# Routerv1_1.net
KiCad netlist of a schematic drawn in EAGLE
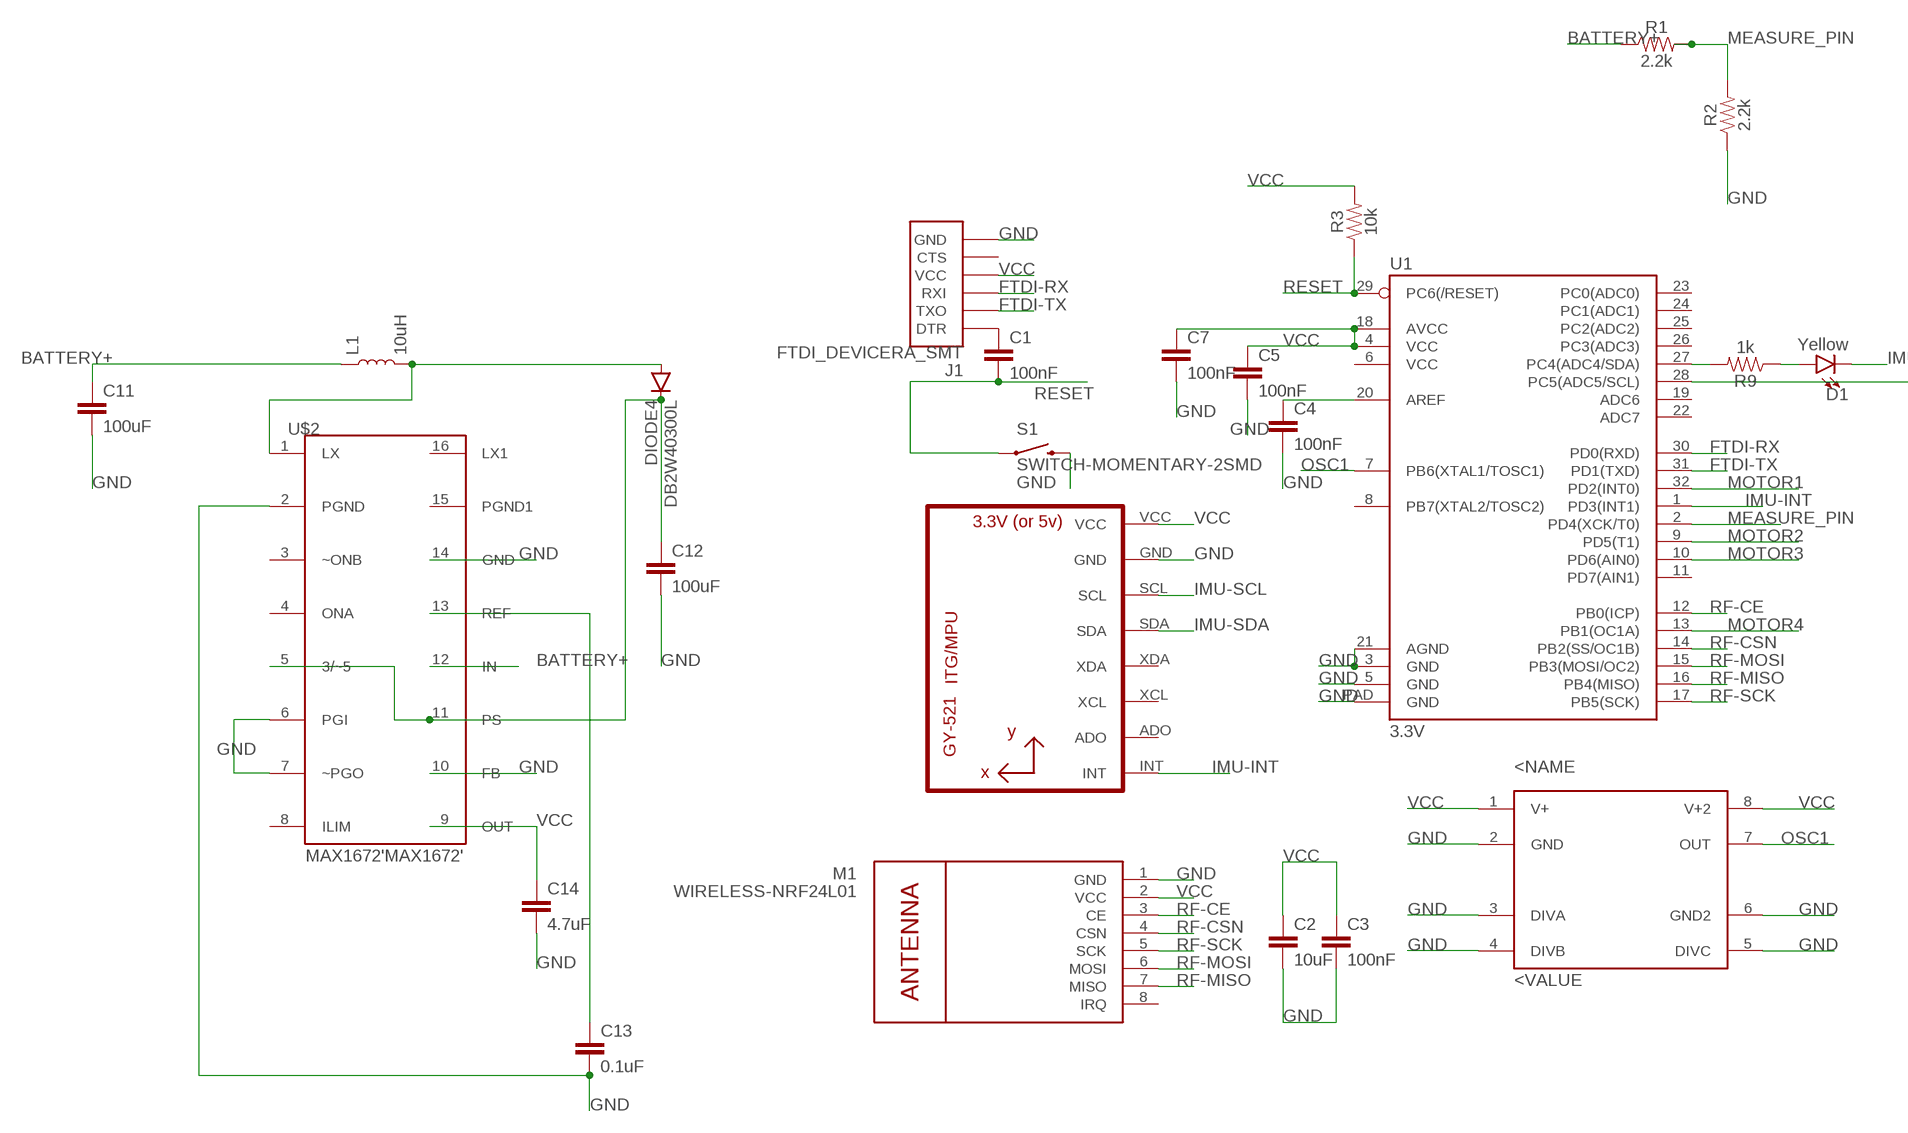
[diagram p0: schematic, sheet 1, part 1 of 2]
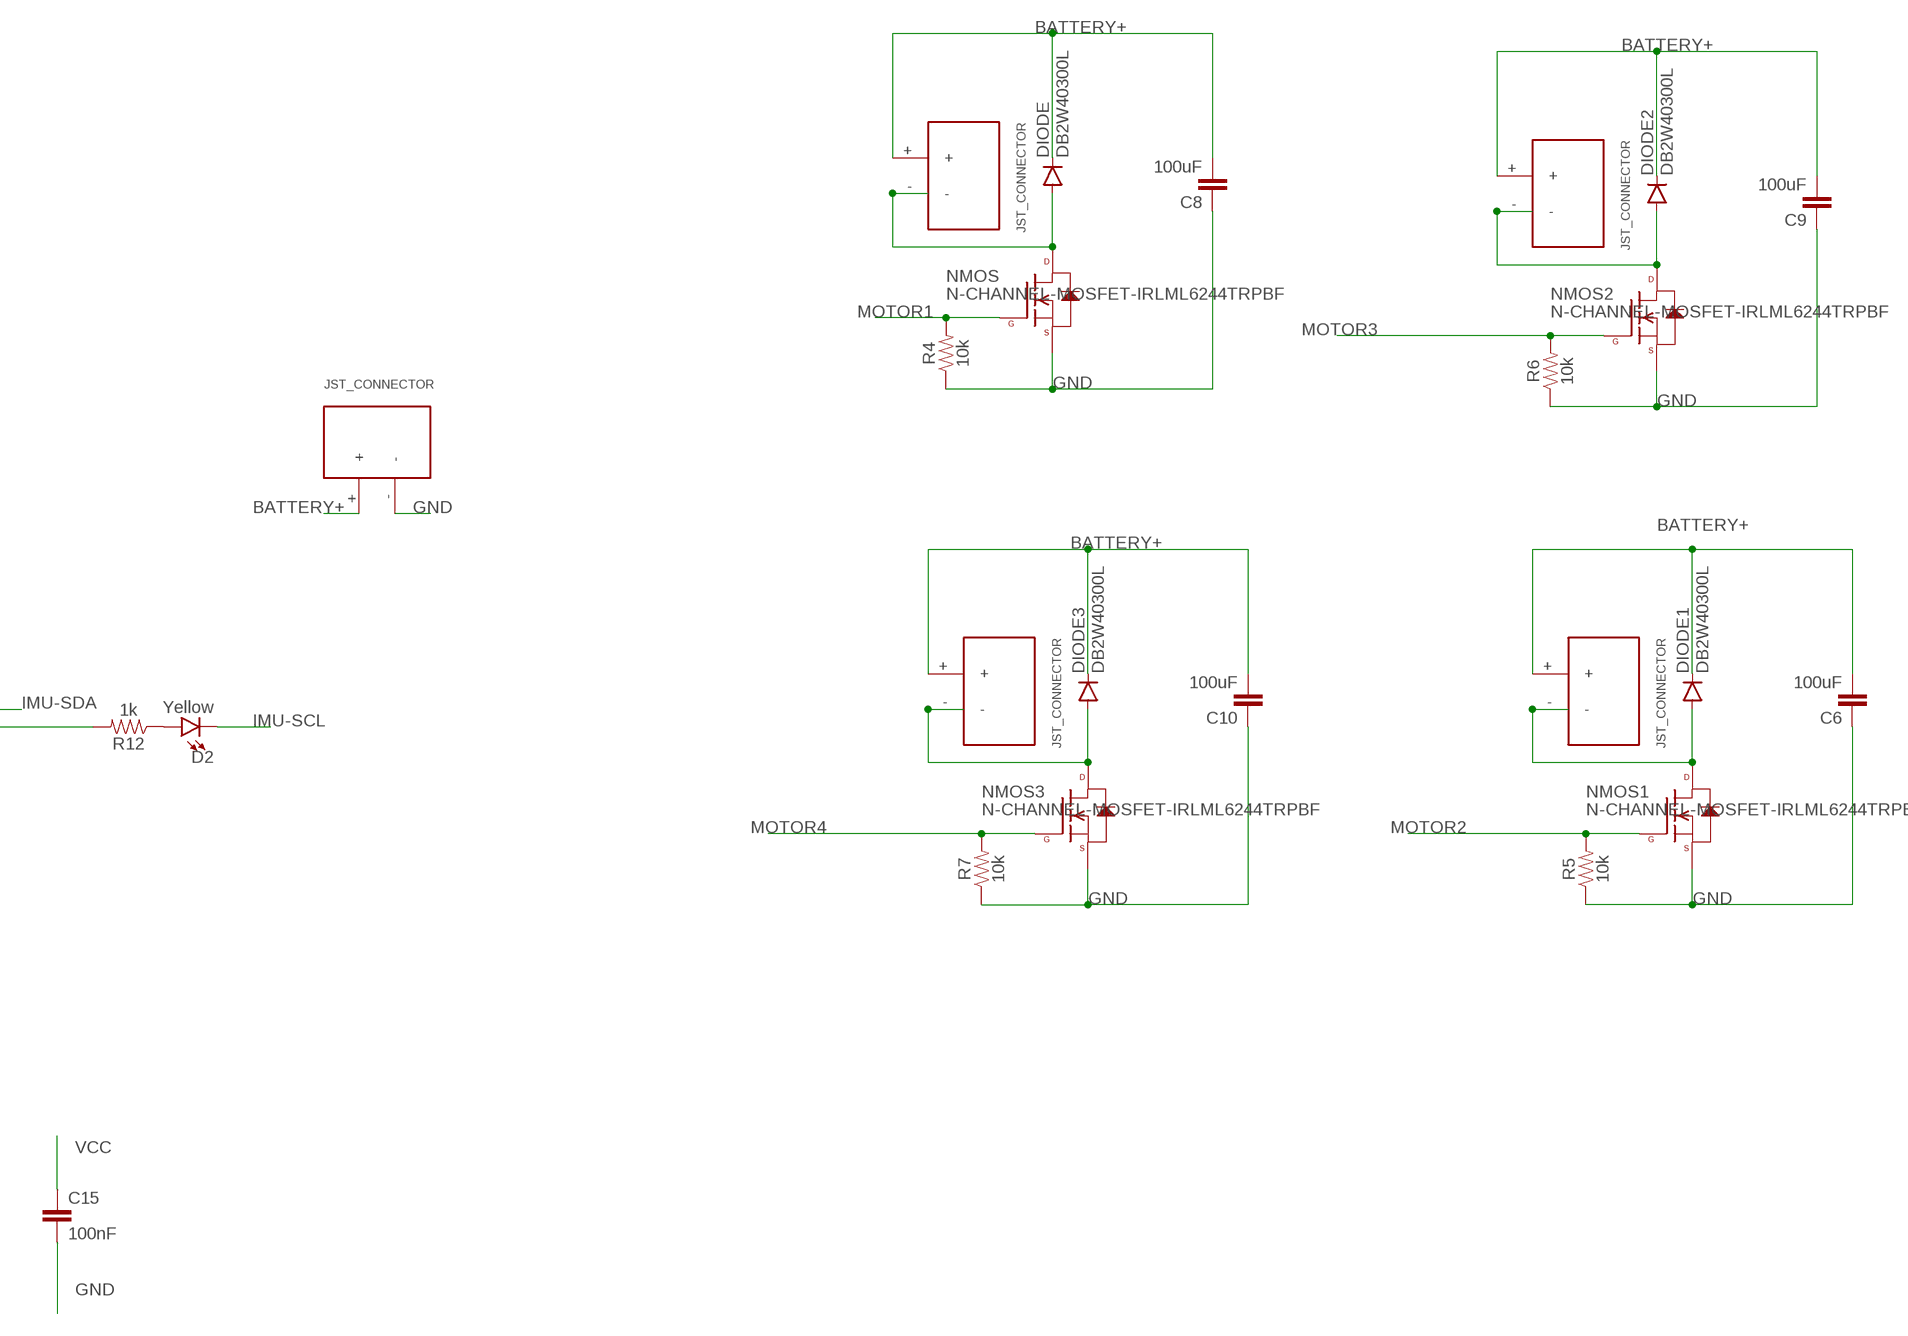
[diagram p1: schematic, sheet 1, part 2 of 2]

(export (version "E")
  (design (tool "Eeschema 10.0.6"))
  (components
    (comp (ref "C1")
      (value "100nF")
      (footprint "eagle-import:0603-CAP")
      (libsource (lib "eagle-import") (part "0.1UF-25V(+80/-20%)(0603)"))
    )
    (comp (ref "C2")
      (value "10uF")
      (footprint "eagle-import:0603-CAP")
      (libsource (lib "eagle-import") (part "CAP0603-CAP"))
    )
    (comp (ref "C3")
      (value "100nF")
      (footprint "eagle-import:0603-CAP")
      (libsource (lib "eagle-import") (part "CAP0603-CAP"))
    )
    (comp (ref "C4")
      (value "100nF")
      (footprint "eagle-import:0603-CAP")
      (libsource (lib "eagle-import") (part "CAP0603-CAP"))
    )
    (comp (ref "C5")
      (value "100nF")
      (footprint "eagle-import:0603-CAP")
      (libsource (lib "eagle-import") (part "CAP0603-CAP"))
    )
    (comp (ref "C6")
      (value "100uF")
      (footprint "eagle-import:0603-CAP")
      (libsource (lib "eagle-import") (part "CAP0603-CAP"))
    )
    (comp (ref "C7")
      (value "100nF")
      (footprint "eagle-import:0603-CAP")
      (libsource (lib "eagle-import") (part "CAP0603-CAP"))
    )
    (comp (ref "C8")
      (value "100uF")
      (footprint "eagle-import:0603-CAP")
      (libsource (lib "eagle-import") (part "CAP0603-CAP"))
    )
    (comp (ref "C9")
      (value "100uF")
      (footprint "eagle-import:0603-CAP")
      (libsource (lib "eagle-import") (part "CAP0603-CAP"))
    )
    (comp (ref "C10")
      (value "100uF")
      (footprint "eagle-import:0603-CAP")
      (libsource (lib "eagle-import") (part "CAP0603-CAP"))
    )
    (comp (ref "C11")
      (value "100uF")
      (footprint "eagle-import:0603-CAP")
      (libsource (lib "eagle-import") (part "CAP0603-CAP"))
    )
    (comp (ref "C12")
      (value "100uF")
      (footprint "eagle-import:0603-CAP")
      (libsource (lib "eagle-import") (part "CAP0603-CAP"))
    )
    (comp (ref "C13")
      (value "0.1uF")
      (footprint "eagle-import:0603-CAP")
      (libsource (lib "eagle-import") (part "CAP0603-CAP"))
    )
    (comp (ref "C14")
      (value "4.7uF")
      (footprint "eagle-import:0603-CAP")
      (libsource (lib "eagle-import") (part "CAP0603-CAP"))
    )
    (comp (ref "C15")
      (value "100nF")
      (footprint "eagle-import:0603-CAP")
      (libsource (lib "eagle-import") (part "0.1UF-25V(+80/-20%)(0603)"))
    )
    (comp (ref "D1")
      (value "Yellow")
      (footprint "eagle-import:LED-1206")
      (libsource (lib "eagle-import") (part "LED-YELLOWLILYPAD"))
    )
    (comp (ref "D2")
      (value "Yellow")
      (footprint "eagle-import:LED-1206")
      (libsource (lib "eagle-import") (part "LED-YELLOWLILYPAD"))
    )
    (comp (ref "DIODE")
      (value "DB2W40300L")
      (footprint "eagle-import:MINI2-F3-B")
      (libsource (lib "eagle-import") (part "DB2W40300L"))
    )
    (comp (ref "DIODE1")
      (value "DB2W40300L")
      (footprint "eagle-import:MINI2-F3-B")
      (libsource (lib "eagle-import") (part "DB2W40300L"))
    )
    (comp (ref "DIODE2")
      (value "DB2W40300L")
      (footprint "eagle-import:MINI2-F3-B")
      (libsource (lib "eagle-import") (part "DB2W40300L"))
    )
    (comp (ref "DIODE3")
      (value "DB2W40300L")
      (footprint "eagle-import:MINI2-F3-B")
      (libsource (lib "eagle-import") (part "DB2W40300L"))
    )
    (comp (ref "DIODE4")
      (value "DB2W40300L")
      (footprint "eagle-import:MINI2-F3-B")
      (libsource (lib "eagle-import") (part "DB2W40300L"))
    )
    (comp (ref "J1")
      (value "FTDI_DEVICERA_SMT")
      (footprint "eagle-import:FTDI_DEVICE_RA_SMT")
      (libsource (lib "eagle-import") (part "FTDI_DEVICERA_SMT"))
    )
    (comp (ref "L1")
      (value "10uH")
      (footprint "eagle-import:0603")
      (libsource (lib "eagle-import") (part "INDUCTOR-0603-33NH"))
    )
    (comp (ref "M1")
      (value "WIRELESS-NRF24L01")
      (footprint "eagle-import:WIRELESS-NRF24L01")
      (libsource (lib "eagle-import") (part "WIRELESS-NRF24L01"))
    )
    (comp (ref "MOTOR")
      (value "JST_CONNECTOR_FEMALE")
      (footprint "eagle-import:JST_CONNECTOR_FEMALE")
      (libsource (lib "eagle-import") (part "JST_CONNECTOR_FEMALE"))
    )
    (comp (ref "MOTOR1")
      (value "JST_CONNECTOR_FEMALE")
      (footprint "eagle-import:JST_CONNECTOR_FEMALE")
      (libsource (lib "eagle-import") (part "JST_CONNECTOR_FEMALE"))
    )
    (comp (ref "MOTOR2")
      (value "JST_CONNECTOR_FEMALE")
      (footprint "eagle-import:JST_CONNECTOR_FEMALE")
      (libsource (lib "eagle-import") (part "JST_CONNECTOR_FEMALE"))
    )
    (comp (ref "MOTOR3")
      (value "JST_CONNECTOR_FEMALE")
      (footprint "eagle-import:JST_CONNECTOR_FEMALE")
      (libsource (lib "eagle-import") (part "JST_CONNECTOR_FEMALE"))
    )
    (comp (ref "NMOS")
      (value "N-CHANNEL-MOSFET-IRLML6244TRPBF")
      (footprint "eagle-import:SOT23-3")
      (libsource (lib "eagle-import") (part "N-CHANNEL-MOSFET-IRLML6244TRPBF"))
    )
    (comp (ref "NMOS1")
      (value "N-CHANNEL-MOSFET-IRLML6244TRPBF")
      (footprint "eagle-import:SOT23-3")
      (libsource (lib "eagle-import") (part "N-CHANNEL-MOSFET-IRLML6244TRPBF"))
    )
    (comp (ref "NMOS2")
      (value "N-CHANNEL-MOSFET-IRLML6244TRPBF")
      (footprint "eagle-import:SOT23-3")
      (libsource (lib "eagle-import") (part "N-CHANNEL-MOSFET-IRLML6244TRPBF"))
    )
    (comp (ref "NMOS3")
      (value "N-CHANNEL-MOSFET-IRLML6244TRPBF")
      (footprint "eagle-import:SOT23-3")
      (libsource (lib "eagle-import") (part "N-CHANNEL-MOSFET-IRLML6244TRPBF"))
    )
    (comp (ref "R1")
      (value "2.2k")
      (footprint "eagle-import:0603")
      (libsource (lib "eagle-import") (part "2.2KOHM-0603-1/10W-1%"))
    )
    (comp (ref "R2")
      (value "2.2k")
      (footprint "eagle-import:0603")
      (libsource (lib "eagle-import") (part "2.2KOHM-0603-1/10W-1%"))
    )
    (comp (ref "R3")
      (value "10k")
      (footprint "eagle-import:0603")
      (libsource (lib "eagle-import") (part "2.2KOHM-0603-1/10W-1%"))
    )
    (comp (ref "R4")
      (value "10k")
      (footprint "eagle-import:0603")
      (libsource (lib "eagle-import") (part "2.2KOHM-0603-1/10W-1%"))
    )
    (comp (ref "R5")
      (value "10k")
      (footprint "eagle-import:0603")
      (libsource (lib "eagle-import") (part "2.2KOHM-0603-1/10W-1%"))
    )
    (comp (ref "R6")
      (value "10k")
      (footprint "eagle-import:0603")
      (libsource (lib "eagle-import") (part "2.2KOHM-0603-1/10W-1%"))
    )
    (comp (ref "R7")
      (value "10k")
      (footprint "eagle-import:0603")
      (libsource (lib "eagle-import") (part "2.2KOHM-0603-1/10W-1%"))
    )
    (comp (ref "R9")
      (value "1k")
      (footprint "eagle-import:0603")
      (libsource (lib "eagle-import") (part "2.2KOHM-0603-1/10W-1%"))
    )
    (comp (ref "R12")
      (value "1k")
      (footprint "eagle-import:0603")
      (libsource (lib "eagle-import") (part "2.2KOHM-0603-1/10W-1%"))
    )
    (comp (ref "S1")
      (value "SWITCH-MOMENTARY-2SMD")
      (footprint "eagle-import:TACTILE-SWITCH-SMD")
      (libsource (lib "eagle-import") (part "SWITCH-MOMENTARY-2SMD"))
    )
    (comp (ref "U$1")
      (value "JST_CONNECTOR_FEMALE")
      (footprint "eagle-import:JST_CONNECTOR_FEMALE")
      (libsource (lib "eagle-import") (part "JST_CONNECTOR_FEMALE"))
    )
    (comp (ref "U$2")
      (value "MAX1672'MAX1672'")
      (footprint "eagle-import:21-0055H_16")
      (libsource (lib "eagle-import") (part "MAX1672'MAX1672'"))
    )
    (comp (ref "U$3")
      (value "LTC6930CMS8-8.19LTC6930CMS8-8.19")
      (footprint "eagle-import:SOP65P490X110-8N")
      (libsource (lib "eagle-import") (part "LTC6930CMS8-8.19LTC6930CMS8-8.19"))
    )
    (comp (ref "U1")
      (value "3.3V")
      (footprint "eagle-import:MLF32-PAD")
      (libsource (lib "eagle-import") (part "ATMEGA328P_MLFMLF32"))
    )
    (comp (ref "U2")
      (value "GY-521MPU6050")
      (footprint "eagle-import:GY-521")
      (libsource (lib "eagle-import") (part "GY-521MPU6050"))
    )
  )
  (nets
    (net (code "1") (name "BATTERY+") (class "Default")
      (node (ref "C10") (pin "2") (pinfunction "2_2") (pintype "passive"))
      (node (ref "C11") (pin "1") (pinfunction "1_1") (pintype "passive"))
      (node (ref "C6") (pin "2") (pinfunction "2_2") (pintype "passive"))
      (node (ref "C8") (pin "2") (pinfunction "2_2") (pintype "passive"))
      (node (ref "C9") (pin "2") (pinfunction "2_2") (pintype "passive"))
      (node (ref "DIODE") (pin "NEG") (pinfunction "GPIN_NEG") (pintype "passive"))
      (node (ref "DIODE1") (pin "NEG") (pinfunction "GPIN_NEG") (pintype "passive"))
      (node (ref "DIODE2") (pin "NEG") (pinfunction "GPIN_NEG") (pintype "passive"))
      (node (ref "DIODE3") (pin "NEG") (pinfunction "GPIN_NEG") (pintype "passive"))
      (node (ref "L1") (pin "1") (pinfunction "1_1") (pintype "passive"))
      (node (ref "MOTOR") (pin "+") (pinfunction "+_+") (pintype "bidirectional"))
      (node (ref "MOTOR1") (pin "+") (pinfunction "+_+") (pintype "bidirectional"))
      (node (ref "MOTOR2") (pin "+") (pinfunction "+_+") (pintype "bidirectional"))
      (node (ref "MOTOR3") (pin "+") (pinfunction "+_+") (pintype "bidirectional"))
      (node (ref "R1") (pin "1") (pinfunction "1_1") (pintype "passive"))
      (node (ref "U$1") (pin "+") (pinfunction "+_+") (pintype "bidirectional"))
      (node (ref "U$2") (pin "12") (pinfunction "IN_12") (pintype "bidirectional"))
    )
    (net (code "2") (name "FTDI-RX") (class "Default")
      (node (ref "J1") (pin "3") (pinfunction "RXI_3") (pintype "bidirectional"))
      (node (ref "U1") (pin "30") (pinfunction "PD0(RXD)_30") (pintype "bidirectional"))
    )
    (net (code "3") (name "FTDI-TX") (class "Default")
      (node (ref "J1") (pin "2") (pinfunction "TXO_2") (pintype "bidirectional"))
      (node (ref "U1") (pin "31") (pinfunction "PD1(TXD)_31") (pintype "bidirectional"))
    )
    (net (code "4") (name "GND") (class "Default")
      (node (ref "C10") (pin "1") (pinfunction "1_1") (pintype "passive"))
      (node (ref "C11") (pin "2") (pinfunction "2_2") (pintype "passive"))
      (node (ref "C12") (pin "2") (pinfunction "2_2") (pintype "passive"))
      (node (ref "C13") (pin "2") (pinfunction "2_2") (pintype "passive"))
      (node (ref "C14") (pin "2") (pinfunction "2_2") (pintype "passive"))
      (node (ref "C15") (pin "2") (pinfunction "2_2") (pintype "passive"))
      (node (ref "C2") (pin "2") (pinfunction "2_2") (pintype "passive"))
      (node (ref "C3") (pin "2") (pinfunction "2_2") (pintype "passive"))
      (node (ref "C4") (pin "2") (pinfunction "2_2") (pintype "passive"))
      (node (ref "C5") (pin "2") (pinfunction "2_2") (pintype "passive"))
      (node (ref "C6") (pin "1") (pinfunction "1_1") (pintype "passive"))
      (node (ref "C7") (pin "2") (pinfunction "2_2") (pintype "passive"))
      (node (ref "C8") (pin "1") (pinfunction "1_1") (pintype "passive"))
      (node (ref "C9") (pin "1") (pinfunction "1_1") (pintype "passive"))
      (node (ref "J1") (pin "6") (pinfunction "GND_6") (pintype "bidirectional"))
      (node (ref "M1") (pin "1") (pinfunction "GND_1") (pintype "power_in"))
      (node (ref "NMOS") (pin "2") (pinfunction "S_2") (pintype "passive"))
      (node (ref "NMOS1") (pin "2") (pinfunction "S_2") (pintype "passive"))
      (node (ref "NMOS2") (pin "2") (pinfunction "S_2") (pintype "passive"))
      (node (ref "NMOS3") (pin "2") (pinfunction "S_2") (pintype "passive"))
      (node (ref "R2") (pin "1") (pinfunction "1_1") (pintype "passive"))
      (node (ref "R4") (pin "1") (pinfunction "1_1") (pintype "passive"))
      (node (ref "R5") (pin "1") (pinfunction "1_1") (pintype "passive"))
      (node (ref "R6") (pin "1") (pinfunction "1_1") (pintype "passive"))
      (node (ref "R7") (pin "1") (pinfunction "1_1") (pintype "passive"))
      (node (ref "S1") (pin "3") (pinfunction "2_3") (pintype "passive"))
      (node (ref "U$1") (pin "-") (pinfunction "-_-") (pintype "bidirectional"))
      (node (ref "U$2") (pin "10") (pinfunction "FB_10") (pintype "bidirectional"))
      (node (ref "U$2") (pin "14") (pinfunction "GND_14") (pintype "bidirectional"))
      (node (ref "U$2") (pin "2") (pinfunction "PGND_2") (pintype "bidirectional"))
      (node (ref "U$2") (pin "6") (pinfunction "PGI_6") (pintype "bidirectional"))
      (node (ref "U$2") (pin "7") (pinfunction "~{PGO}_7") (pintype "bidirectional"))
      (node (ref "U$3") (pin "2") (pinfunction "GND_2") (pintype "bidirectional"))
      (node (ref "U$3") (pin "3") (pinfunction "DIVA_3") (pintype "bidirectional"))
      (node (ref "U$3") (pin "4") (pinfunction "DIVB_4") (pintype "bidirectional"))
      (node (ref "U$3") (pin "5") (pinfunction "DIVC_5") (pintype "bidirectional"))
      (node (ref "U$3") (pin "6") (pinfunction "GND2_6") (pintype "bidirectional"))
      (node (ref "U1") (pin "21") (pinfunction "AGND_21") (pintype "bidirectional"))
      (node (ref "U1") (pin "3") (pinfunction "GND_3") (pintype "bidirectional"))
      (node (ref "U1") (pin "5") (pinfunction "GND_5") (pintype "bidirectional"))
      (node (ref "U1") (pin "PAD") (pinfunction "GND_PAD") (pintype "bidirectional"))
      (node (ref "U2") (pin "GND") (pinfunction "GND_GND") (pintype "bidirectional"))
    )
    (net (code "5") (name "IMU-INT") (class "Default")
      (node (ref "U1") (pin "1") (pinfunction "PD3(INT1)_1") (pintype "bidirectional"))
      (node (ref "U2") (pin "INT") (pinfunction "INT_INT") (pintype "bidirectional"))
    )
    (net (code "6") (name "IMU-SCL") (class "Default")
      (node (ref "D2") (pin "C") (pinfunction "C_C") (pintype "passive"))
      (node (ref "U2") (pin "SCL") (pinfunction "SCL_SCL") (pintype "bidirectional"))
    )
    (net (code "7") (name "IMU-SDA") (class "Default")
      (node (ref "D1") (pin "C") (pinfunction "C_C") (pintype "passive"))
      (node (ref "U2") (pin "SDA") (pinfunction "SDA_SDA") (pintype "bidirectional"))
    )
    (net (code "8") (name "MEASURE_PIN") (class "Default")
      (node (ref "R1") (pin "2") (pinfunction "2_2") (pintype "passive"))
      (node (ref "R2") (pin "2") (pinfunction "2_2") (pintype "passive"))
      (node (ref "U1") (pin "2") (pinfunction "PD4(XCK/T0)_2") (pintype "bidirectional"))
    )
    (net (code "9") (name "MOTOR1") (class "Default")
      (node (ref "NMOS") (pin "1") (pinfunction "G_1") (pintype "passive"))
      (node (ref "R4") (pin "2") (pinfunction "2_2") (pintype "passive"))
      (node (ref "U1") (pin "32") (pinfunction "PD2(INT0)_32") (pintype "bidirectional"))
    )
    (net (code "10") (name "MOTOR2") (class "Default")
      (node (ref "NMOS1") (pin "1") (pinfunction "G_1") (pintype "passive"))
      (node (ref "R5") (pin "2") (pinfunction "2_2") (pintype "passive"))
      (node (ref "U1") (pin "9") (pinfunction "PD5(T1)_9") (pintype "bidirectional"))
    )
    (net (code "11") (name "MOTOR3") (class "Default")
      (node (ref "NMOS2") (pin "1") (pinfunction "G_1") (pintype "passive"))
      (node (ref "R6") (pin "2") (pinfunction "2_2") (pintype "passive"))
      (node (ref "U1") (pin "10") (pinfunction "PD6(AIN0)_10") (pintype "bidirectional"))
    )
    (net (code "12") (name "MOTOR4") (class "Default")
      (node (ref "NMOS3") (pin "1") (pinfunction "G_1") (pintype "passive"))
      (node (ref "R7") (pin "2") (pinfunction "2_2") (pintype "passive"))
      (node (ref "U1") (pin "13") (pinfunction "PB1(OC1A)_13") (pintype "bidirectional"))
    )
    (net (code "13") (name "Net-(D1-PadA)") (class "Default")
      (node (ref "D1") (pin "A") (pinfunction "A_A") (pintype "passive"))
      (node (ref "R9") (pin "1") (pinfunction "1_1") (pintype "passive"))
    )
    (net (code "14") (name "Net-(D2-PadA)") (class "Default")
      (node (ref "D2") (pin "A") (pinfunction "A_A") (pintype "passive"))
      (node (ref "R12") (pin "1") (pinfunction "1_1") (pintype "passive"))
    )
    (net (code "15") (name "Net-(DIODE-PPIN)") (class "Default")
      (node (ref "DIODE") (pin "POS") (pinfunction "PPIN_POS") (pintype "passive"))
      (node (ref "MOTOR") (pin "-") (pinfunction "-_-") (pintype "bidirectional"))
      (node (ref "NMOS") (pin "3") (pinfunction "D_3") (pintype "passive"))
    )
    (net (code "16") (name "Net-(DIODE1-PPIN)") (class "Default")
      (node (ref "DIODE1") (pin "POS") (pinfunction "PPIN_POS") (pintype "passive"))
      (node (ref "MOTOR1") (pin "-") (pinfunction "-_-") (pintype "bidirectional"))
      (node (ref "NMOS1") (pin "3") (pinfunction "D_3") (pintype "passive"))
    )
    (net (code "17") (name "Net-(DIODE2-PPIN)") (class "Default")
      (node (ref "DIODE2") (pin "POS") (pinfunction "PPIN_POS") (pintype "passive"))
      (node (ref "MOTOR2") (pin "-") (pinfunction "-_-") (pintype "bidirectional"))
      (node (ref "NMOS2") (pin "3") (pinfunction "D_3") (pintype "passive"))
    )
    (net (code "18") (name "Net-(DIODE3-PPIN)") (class "Default")
      (node (ref "DIODE3") (pin "POS") (pinfunction "PPIN_POS") (pintype "passive"))
      (node (ref "MOTOR3") (pin "-") (pinfunction "-_-") (pintype "bidirectional"))
      (node (ref "NMOS3") (pin "3") (pinfunction "D_3") (pintype "passive"))
    )
    (net (code "19") (name "Net-(DIODE4-GPIN)") (class "Default")
      (node (ref "C12") (pin "1") (pinfunction "1_1") (pintype "passive"))
      (node (ref "DIODE4") (pin "NEG") (pinfunction "GPIN_NEG") (pintype "passive"))
      (node (ref "U$2") (pin "11") (pinfunction "PS_11") (pintype "bidirectional"))
      (node (ref "U$2") (pin "5") (pinfunction "3/~{5}_5") (pintype "bidirectional"))
    )
    (net (code "20") (name "Net-(DIODE4-PPIN)") (class "Default")
      (node (ref "DIODE4") (pin "POS") (pinfunction "PPIN_POS") (pintype "passive"))
      (node (ref "L1") (pin "2") (pinfunction "2_2") (pintype "passive"))
      (node (ref "U$2") (pin "1") (pinfunction "LX_1") (pintype "bidirectional"))
    )
    (net (code "21") (name "Net-(J1-DTR)") (class "Default")
      (node (ref "C1") (pin "1") (pinfunction "1_1") (pintype "passive"))
      (node (ref "J1") (pin "1") (pinfunction "DTR_1") (pintype "bidirectional"))
    )
    (net (code "22") (name "Net-(U$2-REF)") (class "Default")
      (node (ref "C13") (pin "1") (pinfunction "1_1") (pintype "passive"))
      (node (ref "U$2") (pin "13") (pinfunction "REF_13") (pintype "bidirectional"))
    )
    (net (code "23") (name "Net-(U1-AREF)") (class "Default")
      (node (ref "C4") (pin "1") (pinfunction "1_1") (pintype "passive"))
      (node (ref "U1") (pin "20") (pinfunction "AREF_20") (pintype "bidirectional"))
    )
    (net (code "24") (name "Net-(U1-PC4(ADC4{slash}SDA))") (class "Default")
      (node (ref "R9") (pin "2") (pinfunction "2_2") (pintype "passive"))
      (node (ref "U1") (pin "27") (pinfunction "PC4(ADC4/SDA)_27") (pintype "bidirectional"))
    )
    (net (code "25") (name "Net-(U1-PC5(ADC5{slash}SCL))") (class "Default")
      (node (ref "R12") (pin "2") (pinfunction "2_2") (pintype "passive"))
      (node (ref "U1") (pin "28") (pinfunction "PC5(ADC5/SCL)_28") (pintype "bidirectional"))
    )
    (net (code "26") (name "OSC1") (class "Default")
      (node (ref "U$3") (pin "7") (pinfunction "OUT_7") (pintype "bidirectional"))
      (node (ref "U1") (pin "7") (pinfunction "PB6(XTAL1/TOSC1)_7") (pintype "bidirectional"))
    )
    (net (code "27") (name "RESET") (class "Default")
      (node (ref "C1") (pin "2") (pinfunction "2_2") (pintype "passive"))
      (node (ref "R3") (pin "1") (pinfunction "1_1") (pintype "passive"))
      (node (ref "S1") (pin "1") (pinfunction "1_1") (pintype "passive"))
      (node (ref "U1") (pin "29") (pinfunction "PC6(/RESET)_29") (pintype "bidirectional"))
    )
    (net (code "28") (name "RF-CE") (class "Default")
      (node (ref "M1") (pin "3") (pinfunction "CE_3") (pintype "bidirectional"))
      (node (ref "U1") (pin "12") (pinfunction "PB0(ICP)_12") (pintype "bidirectional"))
    )
    (net (code "29") (name "RF-CSN") (class "Default")
      (node (ref "M1") (pin "4") (pinfunction "CSN_4") (pintype "bidirectional"))
      (node (ref "U1") (pin "14") (pinfunction "PB2(SS/OC1B)_14") (pintype "bidirectional"))
    )
    (net (code "30") (name "RF-MISO") (class "Default")
      (node (ref "M1") (pin "7") (pinfunction "MISO_7") (pintype "bidirectional"))
      (node (ref "U1") (pin "16") (pinfunction "PB4(MISO)_16") (pintype "bidirectional"))
    )
    (net (code "31") (name "RF-MOSI") (class "Default")
      (node (ref "M1") (pin "6") (pinfunction "MOSI_6") (pintype "bidirectional"))
      (node (ref "U1") (pin "15") (pinfunction "PB3(MOSI/OC2)_15") (pintype "bidirectional"))
    )
    (net (code "32") (name "RF-SCK") (class "Default")
      (node (ref "M1") (pin "5") (pinfunction "SCK_5") (pintype "bidirectional"))
      (node (ref "U1") (pin "17") (pinfunction "PB5(SCK)_17") (pintype "bidirectional"))
    )
    (net (code "33") (name "VCC") (class "Default")
      (node (ref "C14") (pin "1") (pinfunction "1_1") (pintype "passive"))
      (node (ref "C15") (pin "1") (pinfunction "1_1") (pintype "passive"))
      (node (ref "C2") (pin "1") (pinfunction "1_1") (pintype "passive"))
      (node (ref "C3") (pin "1") (pinfunction "1_1") (pintype "passive"))
      (node (ref "C5") (pin "1") (pinfunction "1_1") (pintype "passive"))
      (node (ref "C7") (pin "1") (pinfunction "1_1") (pintype "passive"))
      (node (ref "J1") (pin "4") (pinfunction "VCC_4") (pintype "bidirectional"))
      (node (ref "M1") (pin "2") (pinfunction "VCC_2") (pintype "power_in"))
      (node (ref "R3") (pin "2") (pinfunction "2_2") (pintype "passive"))
      (node (ref "U$2") (pin "9") (pinfunction "OUT_9") (pintype "bidirectional"))
      (node (ref "U$3") (pin "1") (pinfunction "V+_1") (pintype "bidirectional"))
      (node (ref "U$3") (pin "8") (pinfunction "V+2_8") (pintype "bidirectional"))
      (node (ref "U1") (pin "18") (pinfunction "AVCC_18") (pintype "bidirectional"))
      (node (ref "U1") (pin "4") (pinfunction "VCC_4") (pintype "bidirectional"))
      (node (ref "U2") (pin "VCC") (pinfunction "VCC_VCC") (pintype "bidirectional"))
    )
    (net (code "34") (name "unconnected-(J1-CTS-Pad5)") (class "Default")
      (node (ref "J1") (pin "5") (pinfunction "CTS_5") (pintype "bidirectional"))
    )
    (net (code "35") (name "unconnected-(M1-IRQ-Pad8)") (class "Default")
      (node (ref "M1") (pin "8") (pinfunction "IRQ_8") (pintype "bidirectional"))
    )
    (net (code "36") (name "unconnected-(U$2-ILIM-Pad8)") (class "Default")
      (node (ref "U$2") (pin "8") (pinfunction "ILIM_8") (pintype "bidirectional"))
    )
    (net (code "37") (name "unconnected-(U$2-LX1-Pad16)") (class "Default")
      (node (ref "U$2") (pin "16") (pinfunction "LX1_16") (pintype "bidirectional"))
    )
    (net (code "38") (name "unconnected-(U$2-ONA-Pad4)") (class "Default")
      (node (ref "U$2") (pin "4") (pinfunction "ONA_4") (pintype "bidirectional"))
    )
    (net (code "39") (name "unconnected-(U$2-PGND1-Pad15)") (class "Default")
      (node (ref "U$2") (pin "15") (pinfunction "PGND1_15") (pintype "bidirectional"))
    )
    (net (code "40") (name "unconnected-(U$2-~{ONB}-Pad3)") (class "Default")
      (node (ref "U$2") (pin "3") (pinfunction "~{ONB}_3") (pintype "bidirectional"))
    )
    (net (code "41") (name "unconnected-(U1-ADC6-Pad19)") (class "Default")
      (node (ref "U1") (pin "19") (pinfunction "ADC6_19") (pintype "bidirectional"))
    )
    (net (code "42") (name "unconnected-(U1-ADC7-Pad22)") (class "Default")
      (node (ref "U1") (pin "22") (pinfunction "ADC7_22") (pintype "bidirectional"))
    )
    (net (code "43") (name "unconnected-(U1-PB7(XTAL2{slash}TOSC2)-Pad8)") (class "Default")
      (node (ref "U1") (pin "8") (pinfunction "PB7(XTAL2/TOSC2)_8") (pintype "bidirectional"))
    )
    (net (code "44") (name "unconnected-(U1-PC0(ADC0)-Pad23)") (class "Default")
      (node (ref "U1") (pin "23") (pinfunction "PC0(ADC0)_23") (pintype "bidirectional"))
    )
    (net (code "45") (name "unconnected-(U1-PC1(ADC1)-Pad24)") (class "Default")
      (node (ref "U1") (pin "24") (pinfunction "PC1(ADC1)_24") (pintype "bidirectional"))
    )
    (net (code "46") (name "unconnected-(U1-PC2(ADC2)-Pad25)") (class "Default")
      (node (ref "U1") (pin "25") (pinfunction "PC2(ADC2)_25") (pintype "bidirectional"))
    )
    (net (code "47") (name "unconnected-(U1-PC3(ADC3)-Pad26)") (class "Default")
      (node (ref "U1") (pin "26") (pinfunction "PC3(ADC3)_26") (pintype "bidirectional"))
    )
    (net (code "48") (name "unconnected-(U1-PD7(AIN1)-Pad11)") (class "Default")
      (node (ref "U1") (pin "11") (pinfunction "PD7(AIN1)_11") (pintype "bidirectional"))
    )
    (net (code "49") (name "unconnected-(U1-VCC-Pad6)") (class "Default")
      (node (ref "U1") (pin "6") (pinfunction "VCC_6") (pintype "bidirectional"))
    )
    (net (code "50") (name "unconnected-(U2-PadADO)") (class "Default")
      (node (ref "U2") (pin "ADO") (pinfunction "ADO_ADO") (pintype "bidirectional"))
    )
    (net (code "51") (name "unconnected-(U2-PadXCL)") (class "Default")
      (node (ref "U2") (pin "XCL") (pinfunction "XCL_XCL") (pintype "bidirectional"))
    )
    (net (code "52") (name "unconnected-(U2-PadXDA)") (class "Default")
      (node (ref "U2") (pin "XDA") (pinfunction "XDA_XDA") (pintype "bidirectional"))
    )
  )
)
